# Clock_distrubution.net
KiCad netlist of a schematic drawn in Altium Designer
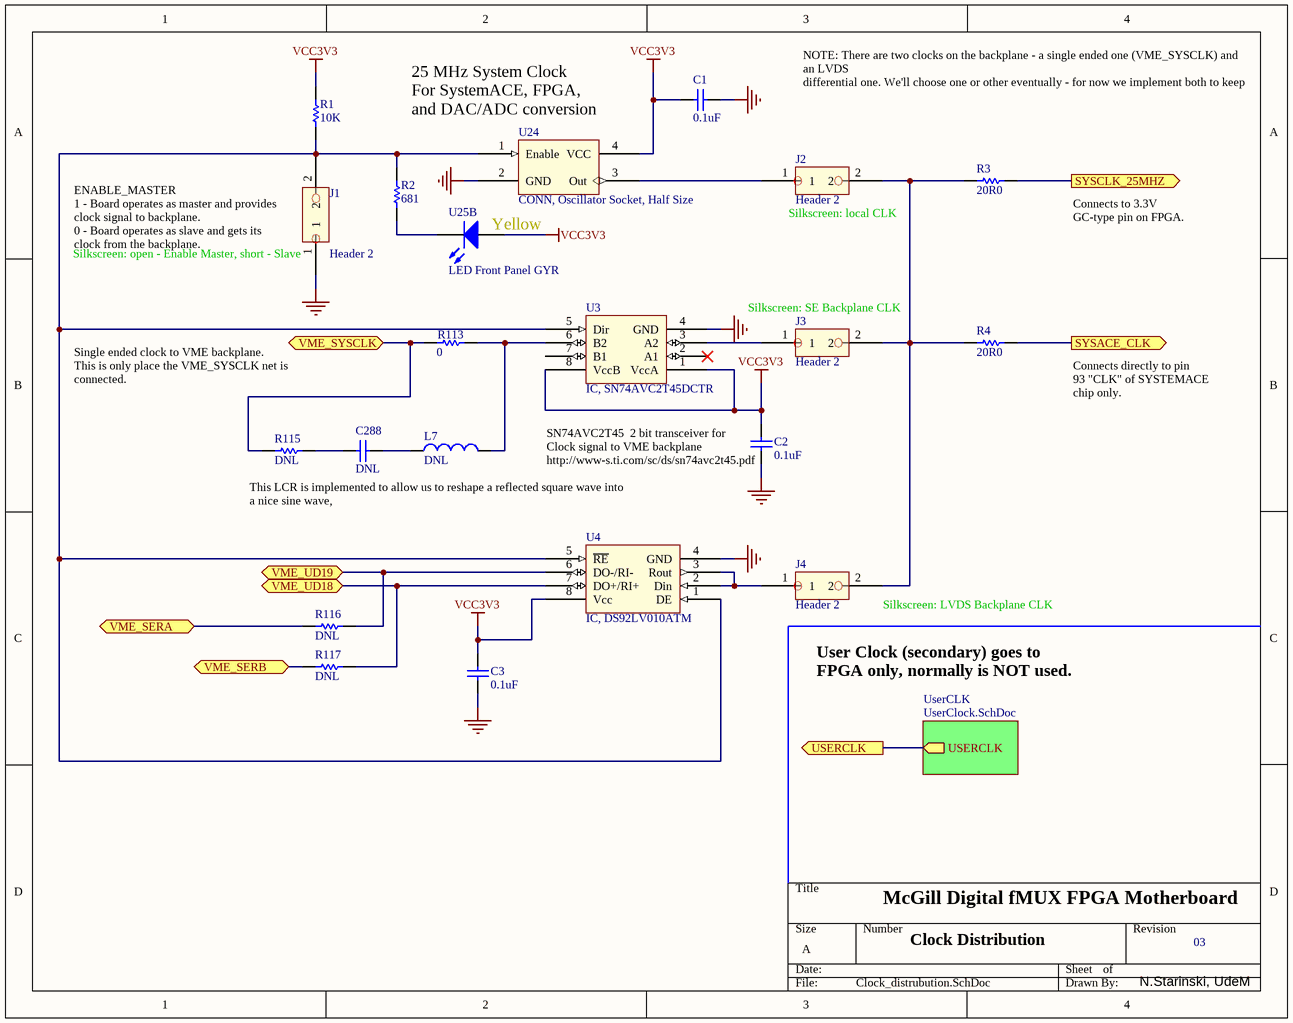
[diagram p0: Clock_distrubution.SchDoc]

(export (version "E")
  (design (tool "Eeschema 10.0.6"))
  (components
    (comp (ref "C1")
      (value "0.1uF")
      (footprint "CC1608-0603")
      (description "Capacitor (Semiconductor SIM Model)")
      (fields (field (name "PUBLISHER") "Altium Limited"))
      (libsource (lib "Miscellaneous Devices") (part "Cap Semi"))
    )
    (comp (ref "C2")
      (value "0.1uF")
      (footprint "CC1608-0603")
      (description "Capacitor (Semiconductor SIM Model)")
      (fields (field (name "PUBLISHER") "Altium Limited"))
      (libsource (lib "Miscellaneous Devices") (part "Cap Semi"))
    )
    (comp (ref "C3")
      (value "0.1uF")
      (footprint "CC1608-0603")
      (description "Capacitor (Semiconductor SIM Model)")
      (fields (field (name "PUBLISHER") "Altium Limited"))
      (libsource (lib "Miscellaneous Devices") (part "Cap Semi"))
    )
    (comp (ref "C288")
      (value "DNL")
      (footprint "CC1608-0603")
      (description "Capacitor (Semiconductor SIM Model)")
      (fields (field (name "PUBLISHER") "Altium Limited"))
      (libsource (lib "Miscellaneous Devices") (part "Cap Semi"))
    )
    (comp (ref "J1")
      (value "Header 2")
      (footprint "HDR1X2")
      (description "Header, 0.1\" 2-Pin straight")
      (libsource (lib "MyComp1") (part "Jumper_100mil"))
    )
    (comp (ref "J2")
      (value "Header 2")
      (footprint "HDR1X2")
      (description "Header, 0.1\" 2-Pin straight")
      (libsource (lib "") (part "Jumper_100mil_1"))
    )
    (comp (ref "J3")
      (value "Header 2")
      (footprint "HDR1X2")
      (description "Header, 0.1\" 2-Pin straight")
      (libsource (lib "") (part "Jumper_100mil_1"))
    )
    (comp (ref "J4")
      (value "Header 2")
      (footprint "HDR1X2")
      (description "Header, 0.1\" 2-Pin straight")
      (libsource (lib "") (part "Jumper_100mil_1"))
    )
    (comp (ref "L7")
      (value "DNL")
      (footprint "INDC2012-0805")
      (description "Inductor")
      (fields (field (name "PUBLISHER") "Altium Limited"))
      (libsource (lib "Miscellaneous Devices") (part "Inductor"))
    )
    (comp (ref "R1")
      (value "10K")
      (footprint "CR1608-0603")
      (description "Resistor 0603")
      (fields (field (name "PUBLISHER") "Altium Limited"))
      (libsource (lib "Miscellaneous Devices") (part "Res Semi"))
    )
    (comp (ref "R2")
      (value "681")
      (footprint "CR1608-0603")
      (description "Resistor 0603")
      (fields (field (name "PUBLISHER") "Altium Limited"))
      (libsource (lib "Miscellaneous Devices") (part "Res Semi"))
    )
    (comp (ref "R3")
      (value "20R0")
      (footprint "CR1608-0603")
      (description "Resistor 0603")
      (fields (field (name "PUBLISHER") "Altium Limited"))
      (libsource (lib "Miscellaneous Devices") (part "Res Semi"))
    )
    (comp (ref "R4")
      (value "20R0")
      (footprint "CR1608-0603")
      (description "Resistor 0603")
      (fields (field (name "PUBLISHER") "Altium Limited"))
      (libsource (lib "Miscellaneous Devices") (part "Res Semi"))
    )
    (comp (ref "R113")
      (value "0")
      (footprint "CR1608-0603")
      (description "Resistor 0603")
      (fields (field (name "PUBLISHER") "Altium Limited"))
      (libsource (lib "Miscellaneous Devices") (part "Res Semi"))
    )
    (comp (ref "R115")
      (value "DNL")
      (footprint "CR1608-0603")
      (description "Semiconductor Resistor")
      (fields (field (name "PUBLISHER") "Altium Limited"))
      (libsource (lib "Miscellaneous Devices") (part "Res Semi"))
    )
    (comp (ref "R116")
      (value "DNL")
      (footprint "CR1608-0603")
      (description "Semiconductor Resistor")
      (fields (field (name "PUBLISHER") "Altium Limited"))
      (libsource (lib "Miscellaneous Devices") (part "Res Semi"))
    )
    (comp (ref "R117")
      (value "DNL")
      (footprint "CR1608-0603")
      (description "Semiconductor Resistor")
      (fields (field (name "PUBLISHER") "Altium Limited"))
      (libsource (lib "Miscellaneous Devices") (part "Res Semi"))
    )
    (comp (ref "U3")
      (value "IC, SN74AVC2T45DCTR")
      (footprint "TSSO3x5-G8/X.35")
      (description "Dual-bit Dual-supply Bus Transceiver")
      (libsource (lib "TI Interface Line Transceiver") (part "SN74AVC2T45"))
    )
    (comp (ref "U4")
      (value "IC, DS92LV010ATM")
      (footprint "SOP8")
      (description "Bus LVDS 3.3/5.0V Single Transceiver")
      (libsource (lib "NSC Interface Line Transceiver") (part "DS92LV010A"))
    )
    (comp (ref "U24")
      (value "CONN, Oscillator Socket, Half Size")
      (footprint "DIP_Osc")
      (description "1108800 ARIES Oscillator Socket")
      (libsource (lib "MyComp1") (part "Osc_Socket"))
    )
    (comp (ref "U25")
      (value "LED Front Panel GYR")
      (footprint "LED_Tri_")
      (description "564-0200-132F")
      (libsource (lib "Miscellaneous Devices") (part "LED_Tri"))
    )
  )
  (nets
    (net (code "1") (name "/SYSACE_CLK") (class "Default")
      (node (ref "R4") (pin "2") (pinfunction "2_2") (pintype "passive"))
    )
    (net (code "2") (name "/SYSCLK_25MHZ") (class "Default")
      (node (ref "R3") (pin "2") (pinfunction "2_2") (pintype "passive"))
    )
    (net (code "4") (name "/VME_SERA") (class "Default")
      (node (ref "R116") (pin "1") (pinfunction "1_1") (pintype "passive"))
    )
    (net (code "5") (name "/VME_SERB") (class "Default")
      (node (ref "R117") (pin "1") (pinfunction "1_1") (pintype "passive"))
    )
    (net (code "6") (name "/VME_SYSCLK") (class "Default")
      (node (ref "R113") (pin "1") (pinfunction "1_1") (pintype "passive"))
      (node (ref "R115") (pin "1") (pinfunction "1_1") (pintype "passive"))
    )
    (net (code "7") (name "/VME_UD18") (class "Default")
      (node (ref "R117") (pin "2") (pinfunction "2_2") (pintype "passive"))
      (node (ref "U4") (pin "7") (pinfunction "DO+/RI+_7") (pintype "bidirectional"))
    )
    (net (code "8") (name "/VME_UD19") (class "Default")
      (node (ref "R116") (pin "2") (pinfunction "2_2") (pintype "passive"))
      (node (ref "U4") (pin "6") (pinfunction "DO-/RI-_6") (pintype "bidirectional"))
    )
    (net (code "9") (name "GND") (class "Default")
      (node (ref "C1") (pin "2") (pinfunction "2_2") (pintype "passive"))
      (node (ref "C2") (pin "1") (pinfunction "1_1") (pintype "passive"))
      (node (ref "C3") (pin "1") (pinfunction "1_1") (pintype "passive"))
      (node (ref "J1") (pin "1") (pinfunction "1_1") (pintype "passive"))
      (node (ref "U24") (pin "2") (pinfunction "GND_2") (pintype "power_in"))
      (node (ref "U3") (pin "4") (pinfunction "GND_4") (pintype "power_in"))
      (node (ref "U4") (pin "4") (pinfunction "GND_4") (pintype "power_in"))
    )
    (net (code "10") (name "Net-(C288-Pad1)") (class "Default")
      (node (ref "C288") (pin "1") (pinfunction "1_1") (pintype "passive"))
      (node (ref "R115") (pin "2") (pinfunction "2_2") (pintype "passive"))
    )
    (net (code "11") (name "Net-(C288-Pad2)") (class "Default")
      (node (ref "C288") (pin "2") (pinfunction "2_2") (pintype "passive"))
      (node (ref "L7") (pin "1") (pinfunction "1_1") (pintype "passive"))
    )
    (net (code "12") (name "Net-(J2-Pad2)") (class "Default")
      (node (ref "J2") (pin "2") (pinfunction "2_2") (pintype "passive"))
      (node (ref "J3") (pin "2") (pinfunction "2_2") (pintype "passive"))
      (node (ref "J4") (pin "2") (pinfunction "2_2") (pintype "passive"))
      (node (ref "R3") (pin "1") (pinfunction "1_1") (pintype "passive"))
      (node (ref "R4") (pin "1") (pinfunction "1_1") (pintype "passive"))
    )
    (net (code "13") (name "Net-(U3-A2)") (class "Default")
      (node (ref "J3") (pin "1") (pinfunction "1_1") (pintype "passive"))
      (node (ref "U3") (pin "3") (pinfunction "A2_3") (pintype "bidirectional"))
    )
    (net (code "14") (name "Net-(U3-B2)") (class "Default")
      (node (ref "L7") (pin "2") (pinfunction "2_2") (pintype "passive"))
      (node (ref "R113") (pin "2") (pinfunction "2_2") (pintype "passive"))
      (node (ref "U3") (pin "6") (pinfunction "B2_6") (pintype "bidirectional"))
    )
    (net (code "15") (name "Net-(U4-Din)") (class "Default")
      (node (ref "J4") (pin "1") (pinfunction "1_1") (pintype "passive"))
      (node (ref "U4") (pin "2") (pinfunction "Din_2") (pintype "input"))
      (node (ref "U4") (pin "3") (pinfunction "Rout_3") (pintype "output"))
    )
    (net (code "16") (name "Net-(U24-Enable)") (class "Default")
      (node (ref "J1") (pin "2") (pinfunction "2_2") (pintype "passive"))
      (node (ref "R1") (pin "1") (pinfunction "1_1") (pintype "passive"))
      (node (ref "R2") (pin "2") (pinfunction "2_2") (pintype "passive"))
      (node (ref "U24") (pin "1") (pinfunction "Enable_1") (pintype "input"))
      (node (ref "U3") (pin "5") (pinfunction "Dir_5") (pintype "input"))
      (node (ref "U4") (pin "1") (pinfunction "DE_1") (pintype "input"))
      (node (ref "U4") (pin "5") (pinfunction "~{RE}_5") (pintype "input"))
    )
    (net (code "17") (name "Net-(U24-Out)") (class "Default")
      (node (ref "J2") (pin "1") (pinfunction "1_1") (pintype "passive"))
      (node (ref "U24") (pin "3") (pinfunction "Out_3") (pintype "output"))
    )
    (net (code "18") (name "Net-(U25B-K)") (class "Default")
      (node (ref "R2") (pin "1") (pinfunction "1_1") (pintype "passive"))
      (node (ref "U25") (pin "K2") (pinfunction "K_K2") (pintype "passive"))
    )
    (net (code "19") (name "VCC3V3") (class "Default")
      (node (ref "C1") (pin "1") (pinfunction "1_1") (pintype "passive"))
      (node (ref "C2") (pin "2") (pinfunction "2_2") (pintype "passive"))
      (node (ref "C3") (pin "2") (pinfunction "2_2") (pintype "passive"))
      (node (ref "R1") (pin "2") (pinfunction "2_2") (pintype "passive"))
      (node (ref "U24") (pin "4") (pinfunction "VCC_4") (pintype "power_in"))
      (node (ref "U25") (pin "A2") (pinfunction "A_A2") (pintype "passive"))
      (node (ref "U3") (pin "1") (pinfunction "VccA_1") (pintype "power_in"))
      (node (ref "U3") (pin "8") (pinfunction "VccB_8") (pintype "power_in"))
      (node (ref "U4") (pin "8") (pinfunction "Vcc_8") (pintype "power_in"))
    )
    (net (code "20") (name "unconnected-(U3-A1-Pad2)") (class "Default")
      (node (ref "U3") (pin "2") (pinfunction "A1_2") (pintype "bidirectional+no_connect"))
    )
    (net (code "21") (name "unconnected-(U3-B1-Pad7)") (class "Default")
      (node (ref "U3") (pin "7") (pinfunction "B1_7") (pintype "bidirectional"))
    )
  )
)
